# pic_tftp100_v2.net
KiCad netlist of a schematic drawn in EAGLE
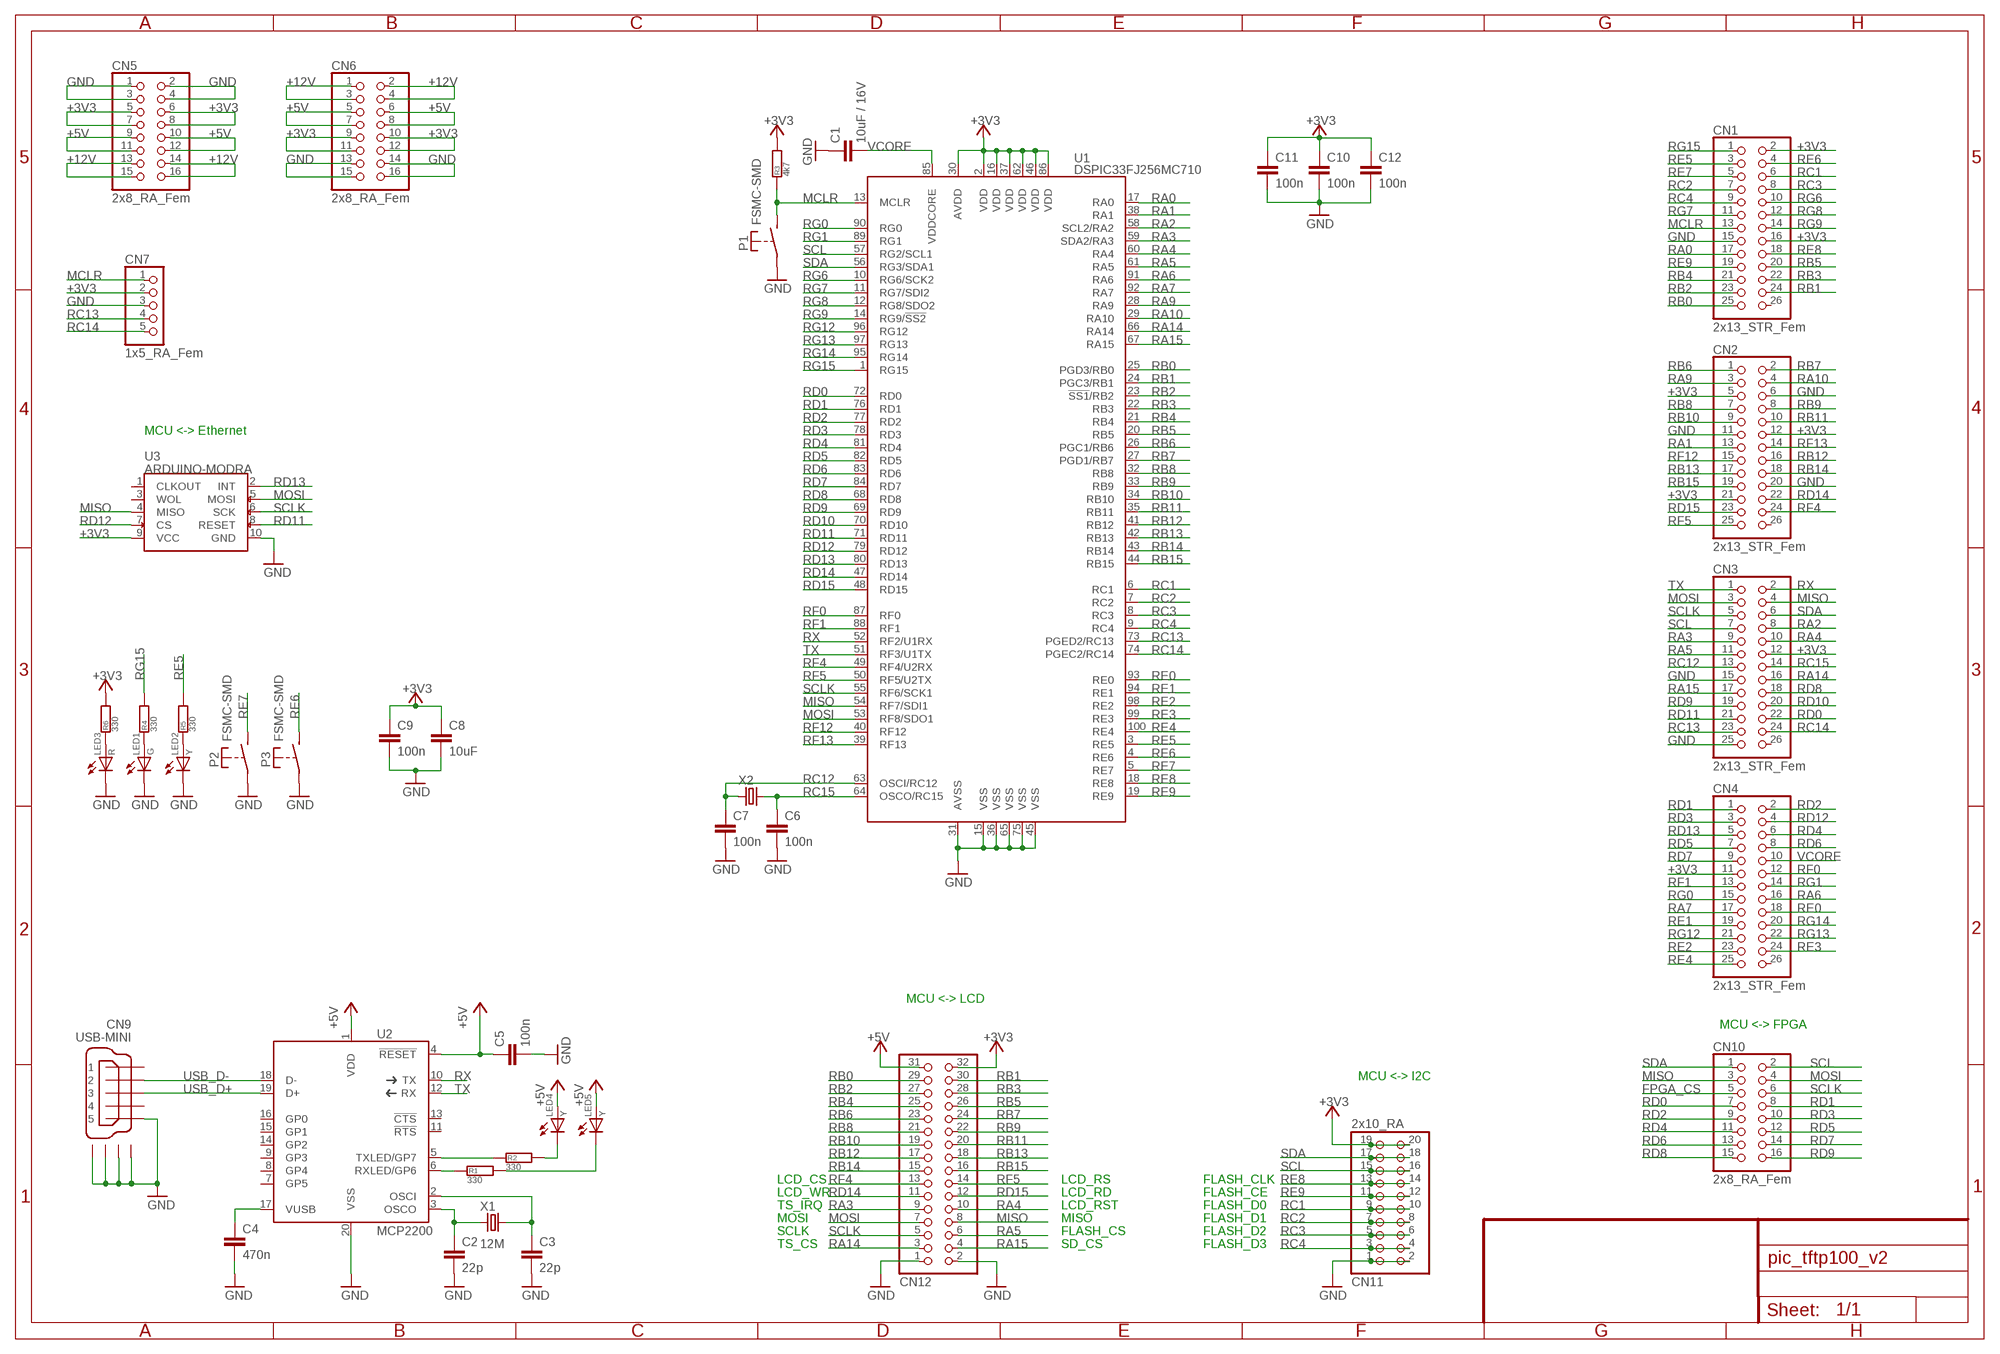
[diagram p0: schematic, sheet 1]

(export (version "E")
  (design (tool "Eeschema 10.0.6"))
  (components
    (comp (ref "C1")
      (value "10uF / 16V")
      (footprint "eagle-import:C1206")
      (libsource (lib "eagle-import") (part "CONDENSATEURSC1206"))
    )
    (comp (ref "C2")
      (value "22p")
      (footprint "eagle-import:C1206")
      (libsource (lib "eagle-import") (part "CONDENSATEURSC1206"))
    )
    (comp (ref "C3")
      (value "22p")
      (footprint "eagle-import:C1206")
      (libsource (lib "eagle-import") (part "CONDENSATEURSC1206"))
    )
    (comp (ref "C4")
      (value "470n")
      (footprint "eagle-import:C1206")
      (libsource (lib "eagle-import") (part "CONDENSATEURSC1206"))
    )
    (comp (ref "C5")
      (value "100n")
      (footprint "eagle-import:C1206")
      (libsource (lib "eagle-import") (part "CONDENSATEURSC1206"))
    )
    (comp (ref "C6")
      (value "100n")
      (footprint "eagle-import:C1206")
      (libsource (lib "eagle-import") (part "CONDENSATEURSC1206"))
    )
    (comp (ref "C7")
      (value "100n")
      (footprint "eagle-import:C1206")
      (libsource (lib "eagle-import") (part "CONDENSATEURSC1206"))
    )
    (comp (ref "C8")
      (value "10uF")
      (footprint "eagle-import:C1206")
      (libsource (lib "eagle-import") (part "CAPAC1206"))
    )
    (comp (ref "C9")
      (value "100n")
      (footprint "eagle-import:C1206")
      (libsource (lib "eagle-import") (part "CONDENSATEURSC1206"))
    )
    (comp (ref "C10")
      (value "100n")
      (footprint "eagle-import:C1206")
      (libsource (lib "eagle-import") (part "CONDENSATEURSC1206"))
    )
    (comp (ref "C11")
      (value "100n")
      (footprint "eagle-import:C1206")
      (libsource (lib "eagle-import") (part "CONDENSATEURSC1206"))
    )
    (comp (ref "C12")
      (value "100n")
      (footprint "eagle-import:C1206")
      (libsource (lib "eagle-import") (part "CONDENSATEURSC1206"))
    )
    (comp (ref "CN1")
      (value "2x13_STR_Fem")
      (footprint "eagle-import:2X13")
      (libsource (lib "eagle-import") (part "PINHD-2X13_2.54"))
    )
    (comp (ref "CN2")
      (value "2x13_STR_Fem")
      (footprint "eagle-import:2X13")
      (libsource (lib "eagle-import") (part "PINHD-2X13_2.54"))
    )
    (comp (ref "CN3")
      (value "2x13_STR_Fem")
      (footprint "eagle-import:2X13")
      (libsource (lib "eagle-import") (part "PINHD-2X13_2.54"))
    )
    (comp (ref "CN4")
      (value "2x13_STR_Fem")
      (footprint "eagle-import:2X13")
      (libsource (lib "eagle-import") (part "PINHD-2X13_2.54"))
    )
    (comp (ref "CN5")
      (value "2x8_RA_Fem")
      (footprint "eagle-import:2X08_90")
      (libsource (lib "eagle-import") (part "PINHD-2X8_2.54-90°"))
    )
    (comp (ref "CN6")
      (value "2x8_RA_Fem")
      (footprint "eagle-import:2X08_90")
      (libsource (lib "eagle-import") (part "PINHD-2X8_2.54-90°"))
    )
    (comp (ref "CN7")
      (value "1x5_RA_Fem")
      (footprint "eagle-import:1X05_90")
      (libsource (lib "eagle-import") (part "PINHD-1X5_2.54-90°"))
    )
    (comp (ref "CN9")
      (value "USB-MINI")
      (footprint "eagle-import:USB-MINI-SMT")
      (libsource (lib "eagle-import") (part "USB-MINI"))
    )
    (comp (ref "CN10")
      (value "2x8_RA_Fem")
      (footprint "eagle-import:2X08_90")
      (libsource (lib "eagle-import") (part "PINHD-2X8_2.54-90°"))
    )
    (comp (ref "CN11")
      (value "2x10_RA")
      (footprint "eagle-import:2X10_90")
      (libsource (lib "eagle-import") (part "PINHD-2X10_2.54-90°"))
    )
    (comp (ref "CN12")
      (value "PINHD-2X16_2.54-90°")
      (footprint "eagle-import:2X16_90")
      (libsource (lib "eagle-import") (part "PINHD-2X16_2.54-90°"))
    )
    (comp (ref "LED1")
      (value "G")
      (footprint "eagle-import:LED3MM")
      (libsource (lib "eagle-import") (part "LED3MM"))
    )
    (comp (ref "LED2")
      (value "Y")
      (footprint "eagle-import:LED3MM")
      (libsource (lib "eagle-import") (part "LED3MM"))
    )
    (comp (ref "LED3")
      (value "R")
      (footprint "eagle-import:LED3MM")
      (libsource (lib "eagle-import") (part "LED3MM"))
    )
    (comp (ref "LED4")
      (value "Y")
      (footprint "eagle-import:LED3MM")
      (libsource (lib "eagle-import") (part "LED3MM"))
    )
    (comp (ref "LED5")
      (value "Y")
      (footprint "eagle-import:LED3MM")
      (libsource (lib "eagle-import") (part "LED3MM"))
    )
    (comp (ref "P1")
      (value "FSMC-SMD")
      (footprint "eagle-import:FSMC-SMD")
      (libsource (lib "eagle-import") (part "FSMC-SMD"))
    )
    (comp (ref "P2")
      (value "FSMC-SMD")
      (footprint "eagle-import:FSMC-SMD")
      (libsource (lib "eagle-import") (part "FSMC-SMD"))
    )
    (comp (ref "P3")
      (value "FSMC-SMD")
      (footprint "eagle-import:FSMC-SMD")
      (libsource (lib "eagle-import") (part "FSMC-SMD"))
    )
    (comp (ref "R1")
      (value "330")
      (footprint "eagle-import:R1206")
      (libsource (lib "eagle-import") (part "RESISTANCESR1206"))
    )
    (comp (ref "R2")
      (value "330")
      (footprint "eagle-import:R1206")
      (libsource (lib "eagle-import") (part "RESISTANCESR1206"))
    )
    (comp (ref "R3")
      (value "4k7")
      (footprint "eagle-import:R1206")
      (libsource (lib "eagle-import") (part "RESISTANCESR1206"))
    )
    (comp (ref "R4")
      (value "330")
      (footprint "eagle-import:R1206")
      (libsource (lib "eagle-import") (part "RESISTANCESR1206"))
    )
    (comp (ref "R5")
      (value "330")
      (footprint "eagle-import:R1206")
      (libsource (lib "eagle-import") (part "RESISTANCESR1206"))
    )
    (comp (ref "R6")
      (value "330")
      (footprint "eagle-import:R1206")
      (libsource (lib "eagle-import") (part "RESISTANCESR1206"))
    )
    (comp (ref "U1")
      (value "DSPIC33FJ256MC710")
      (footprint "eagle-import:TQFP100")
      (libsource (lib "eagle-import") (part "DSPIC33FJ256MC710"))
    )
    (comp (ref "U2")
      (value "MCP2200")
      (footprint "eagle-import:SOIC20L")
      (libsource (lib "eagle-import") (part "MCP2200"))
    )
    (comp (ref "U3")
      (value "ARDUINO-MODRA")
      (footprint "eagle-import:ARDUINO_MOD_RIGHT_ANGLE")
      (libsource (lib "eagle-import") (part "ARDUINO-MODRA"))
    )
    (comp (ref "X1")
      (value "12M")
      (footprint "eagle-import:SMD2_50X32")
      (libsource (lib "eagle-import") (part "CRYSTALSMD2_50X32"))
    )
    (comp (ref "X2")
      (value "CRYSTALSMD2_50X32")
      (footprint "eagle-import:SMD2_50X32")
      (libsource (lib "eagle-import") (part "CRYSTALSMD2_50X32"))
    )
  )
  (nets
    (net (code "1") (name "+3V3") (class "Default")
      (node (ref "C10") (pin "1") (pinfunction "1_1") (pintype "passive"))
      (node (ref "C11") (pin "1") (pinfunction "1_1") (pintype "passive"))
      (node (ref "C12") (pin "1") (pinfunction "1_1") (pintype "passive"))
      (node (ref "C8") (pin "1") (pinfunction "1_1") (pintype "passive"))
      (node (ref "C9") (pin "1") (pinfunction "1_1") (pintype "passive"))
      (node (ref "CN1") (pin "16") (pinfunction "16_16") (pintype "passive"))
      (node (ref "CN1") (pin "2") (pinfunction "2_2") (pintype "passive"))
      (node (ref "CN11") (pin "19") (pinfunction "19_19") (pintype "passive"))
      (node (ref "CN11") (pin "20") (pinfunction "20_20") (pintype "passive"))
      (node (ref "CN12") (pin "32") (pinfunction "32_32") (pintype "passive"))
      (node (ref "CN2") (pin "12") (pinfunction "12_12") (pintype "passive"))
      (node (ref "CN2") (pin "21") (pinfunction "21_21") (pintype "passive"))
      (node (ref "CN2") (pin "5") (pinfunction "5_5") (pintype "passive"))
      (node (ref "CN3") (pin "12") (pinfunction "12_12") (pintype "passive"))
      (node (ref "CN4") (pin "11") (pinfunction "11_11") (pintype "passive"))
      (node (ref "CN5") (pin "5") (pinfunction "5_5") (pintype "passive"))
      (node (ref "CN5") (pin "6") (pinfunction "6_6") (pintype "passive"))
      (node (ref "CN5") (pin "7") (pinfunction "7_7") (pintype "passive"))
      (node (ref "CN5") (pin "8") (pinfunction "8_8") (pintype "passive"))
      (node (ref "CN6") (pin "10") (pinfunction "10_10") (pintype "passive"))
      (node (ref "CN6") (pin "11") (pinfunction "11_11") (pintype "passive"))
      (node (ref "CN6") (pin "12") (pinfunction "12_12") (pintype "passive"))
      (node (ref "CN6") (pin "9") (pinfunction "9_9") (pintype "passive"))
      (node (ref "CN7") (pin "2") (pinfunction "2_2") (pintype "passive"))
      (node (ref "R3") (pin "2") (pinfunction "2_2") (pintype "passive"))
      (node (ref "R6") (pin "2") (pinfunction "2_2") (pintype "passive"))
      (node (ref "U1") (pin "16") (pinfunction "VDD_16") (pintype "power_in"))
      (node (ref "U1") (pin "2") (pinfunction "VDD_2") (pintype "power_in"))
      (node (ref "U1") (pin "30") (pinfunction "AVDD_30") (pintype "power_in"))
      (node (ref "U1") (pin "37") (pinfunction "VDD_37") (pintype "power_in"))
      (node (ref "U1") (pin "46") (pinfunction "VDD_46") (pintype "power_in"))
      (node (ref "U1") (pin "62") (pinfunction "VDD_62") (pintype "power_in"))
      (node (ref "U1") (pin "86") (pinfunction "VDD_86") (pintype "power_in"))
      (node (ref "U3") (pin "9") (pinfunction "VCC_9") (pintype "power_in"))
    )
    (net (code "2") (name "+5V") (class "Default")
      (node (ref "C5") (pin "1") (pinfunction "1_1") (pintype "passive"))
      (node (ref "CN12") (pin "31") (pinfunction "31_31") (pintype "passive"))
      (node (ref "CN5") (pin "10") (pinfunction "10_10") (pintype "passive"))
      (node (ref "CN5") (pin "11") (pinfunction "11_11") (pintype "passive"))
      (node (ref "CN5") (pin "12") (pinfunction "12_12") (pintype "passive"))
      (node (ref "CN5") (pin "9") (pinfunction "9_9") (pintype "passive"))
      (node (ref "CN6") (pin "5") (pinfunction "5_5") (pintype "passive"))
      (node (ref "CN6") (pin "6") (pinfunction "6_6") (pintype "passive"))
      (node (ref "CN6") (pin "7") (pinfunction "7_7") (pintype "passive"))
      (node (ref "CN6") (pin "8") (pinfunction "8_8") (pintype "passive"))
      (node (ref "LED4") (pin "A") (pinfunction "A_A") (pintype "passive"))
      (node (ref "LED5") (pin "A") (pinfunction "A_A") (pintype "passive"))
      (node (ref "U2") (pin "1") (pinfunction "VDD_1") (pintype "power_in"))
      (node (ref "U2") (pin "4") (pinfunction "~{RESET}_4") (pintype "input"))
    )
    (net (code "3") (name "/+12V") (class "Default")
      (node (ref "CN5") (pin "13") (pinfunction "13_13") (pintype "passive"))
      (node (ref "CN5") (pin "14") (pinfunction "14_14") (pintype "passive"))
      (node (ref "CN5") (pin "15") (pinfunction "15_15") (pintype "passive"))
      (node (ref "CN5") (pin "16") (pinfunction "16_16") (pintype "passive"))
      (node (ref "CN6") (pin "1") (pinfunction "1_1") (pintype "passive"))
      (node (ref "CN6") (pin "2") (pinfunction "2_2") (pintype "passive"))
      (node (ref "CN6") (pin "3") (pinfunction "3_3") (pintype "passive"))
      (node (ref "CN6") (pin "4") (pinfunction "4_4") (pintype "passive"))
    )
    (net (code "4") (name "/FPGA_CS") (class "Default")
      (node (ref "CN10") (pin "5") (pinfunction "5_5") (pintype "passive"))
    )
    (net (code "5") (name "/MCLR") (class "Default")
      (node (ref "CN1") (pin "13") (pinfunction "13_13") (pintype "passive"))
      (node (ref "CN7") (pin "1") (pinfunction "1_1") (pintype "passive"))
      (node (ref "P1") (pin "P$2") (pinfunction "S_P$2") (pintype "passive"))
      (node (ref "R3") (pin "1") (pinfunction "1_1") (pintype "passive"))
      (node (ref "U1") (pin "13") (pinfunction "MCLR_13") (pintype "bidirectional"))
    )
    (net (code "6") (name "/MISO") (class "Default")
      (node (ref "CN10") (pin "3") (pinfunction "3_3") (pintype "passive"))
      (node (ref "CN12") (pin "8") (pinfunction "8_8") (pintype "passive"))
      (node (ref "CN3") (pin "4") (pinfunction "4_4") (pintype "passive"))
      (node (ref "U1") (pin "54") (pinfunction "RF7/SDI1_54") (pintype "bidirectional"))
      (node (ref "U3") (pin "4") (pinfunction "MISO_4") (pintype "output"))
    )
    (net (code "7") (name "/MOSI") (class "Default")
      (node (ref "CN10") (pin "4") (pinfunction "4_4") (pintype "passive"))
      (node (ref "CN12") (pin "7") (pinfunction "7_7") (pintype "passive"))
      (node (ref "CN3") (pin "3") (pinfunction "3_3") (pintype "passive"))
      (node (ref "U1") (pin "53") (pinfunction "RF8/SDO1_53") (pintype "bidirectional"))
      (node (ref "U3") (pin "5") (pinfunction "MOSI_5") (pintype "input"))
    )
    (net (code "8") (name "/RA0") (class "Default")
      (node (ref "CN1") (pin "17") (pinfunction "17_17") (pintype "passive"))
      (node (ref "U1") (pin "17") (pinfunction "RA0_17") (pintype "bidirectional"))
    )
    (net (code "9") (name "/RA1") (class "Default")
      (node (ref "CN2") (pin "13") (pinfunction "13_13") (pintype "passive"))
      (node (ref "U1") (pin "38") (pinfunction "RA1_38") (pintype "bidirectional"))
    )
    (net (code "10") (name "/RA2") (class "Default")
      (node (ref "CN3") (pin "8") (pinfunction "8_8") (pintype "passive"))
      (node (ref "U1") (pin "58") (pinfunction "SCL2/RA2_58") (pintype "bidirectional"))
    )
    (net (code "11") (name "/RA3") (class "Default")
      (node (ref "CN12") (pin "9") (pinfunction "9_9") (pintype "passive"))
      (node (ref "CN3") (pin "9") (pinfunction "9_9") (pintype "passive"))
      (node (ref "U1") (pin "59") (pinfunction "SDA2/RA3_59") (pintype "bidirectional"))
    )
    (net (code "12") (name "/RA4") (class "Default")
      (node (ref "CN12") (pin "10") (pinfunction "10_10") (pintype "passive"))
      (node (ref "CN3") (pin "10") (pinfunction "10_10") (pintype "passive"))
      (node (ref "U1") (pin "60") (pinfunction "RA4_60") (pintype "bidirectional"))
    )
    (net (code "13") (name "/RA5") (class "Default")
      (node (ref "CN12") (pin "6") (pinfunction "6_6") (pintype "passive"))
      (node (ref "CN3") (pin "11") (pinfunction "11_11") (pintype "passive"))
      (node (ref "U1") (pin "61") (pinfunction "RA5_61") (pintype "bidirectional"))
    )
    (net (code "14") (name "/RA6") (class "Default")
      (node (ref "CN4") (pin "16") (pinfunction "16_16") (pintype "passive"))
      (node (ref "U1") (pin "91") (pinfunction "RA6_91") (pintype "bidirectional"))
    )
    (net (code "15") (name "/RA7") (class "Default")
      (node (ref "CN4") (pin "17") (pinfunction "17_17") (pintype "passive"))
      (node (ref "U1") (pin "92") (pinfunction "RA7_92") (pintype "bidirectional"))
    )
    (net (code "16") (name "/RA9") (class "Default")
      (node (ref "CN2") (pin "3") (pinfunction "3_3") (pintype "passive"))
      (node (ref "U1") (pin "28") (pinfunction "RA9_28") (pintype "bidirectional"))
    )
    (net (code "17") (name "/RA10") (class "Default")
      (node (ref "CN2") (pin "4") (pinfunction "4_4") (pintype "passive"))
      (node (ref "U1") (pin "29") (pinfunction "RA10_29") (pintype "bidirectional"))
    )
    (net (code "18") (name "/RA14") (class "Default")
      (node (ref "CN12") (pin "3") (pinfunction "3_3") (pintype "passive"))
      (node (ref "CN3") (pin "16") (pinfunction "16_16") (pintype "passive"))
      (node (ref "U1") (pin "66") (pinfunction "RA14_66") (pintype "bidirectional"))
    )
    (net (code "19") (name "/RA15") (class "Default")
      (node (ref "CN12") (pin "4") (pinfunction "4_4") (pintype "passive"))
      (node (ref "CN3") (pin "17") (pinfunction "17_17") (pintype "passive"))
      (node (ref "U1") (pin "67") (pinfunction "RA15_67") (pintype "bidirectional"))
    )
    (net (code "20") (name "/RB0") (class "Default")
      (node (ref "CN1") (pin "25") (pinfunction "25_25") (pintype "passive"))
      (node (ref "CN12") (pin "29") (pinfunction "29_29") (pintype "passive"))
      (node (ref "U1") (pin "25") (pinfunction "PGD3/RB0_25") (pintype "bidirectional"))
    )
    (net (code "21") (name "/RB1") (class "Default")
      (node (ref "CN1") (pin "24") (pinfunction "24_24") (pintype "passive"))
      (node (ref "CN12") (pin "30") (pinfunction "30_30") (pintype "passive"))
      (node (ref "U1") (pin "24") (pinfunction "PGC3/RB1_24") (pintype "bidirectional"))
    )
    (net (code "22") (name "/RB2") (class "Default")
      (node (ref "CN1") (pin "23") (pinfunction "23_23") (pintype "passive"))
      (node (ref "CN12") (pin "27") (pinfunction "27_27") (pintype "passive"))
      (node (ref "U1") (pin "23") (pinfunction "~{SS1}/RB2_23") (pintype "bidirectional"))
    )
    (net (code "23") (name "/RB3") (class "Default")
      (node (ref "CN1") (pin "22") (pinfunction "22_22") (pintype "passive"))
      (node (ref "CN12") (pin "28") (pinfunction "28_28") (pintype "passive"))
      (node (ref "U1") (pin "22") (pinfunction "RB3_22") (pintype "bidirectional"))
    )
    (net (code "24") (name "/RB4") (class "Default")
      (node (ref "CN1") (pin "21") (pinfunction "21_21") (pintype "passive"))
      (node (ref "CN12") (pin "25") (pinfunction "25_25") (pintype "passive"))
      (node (ref "U1") (pin "21") (pinfunction "RB4_21") (pintype "bidirectional"))
    )
    (net (code "25") (name "/RB5") (class "Default")
      (node (ref "CN1") (pin "20") (pinfunction "20_20") (pintype "passive"))
      (node (ref "CN12") (pin "26") (pinfunction "26_26") (pintype "passive"))
      (node (ref "U1") (pin "20") (pinfunction "RB5_20") (pintype "bidirectional"))
    )
    (net (code "26") (name "/RB6") (class "Default")
      (node (ref "CN12") (pin "23") (pinfunction "23_23") (pintype "passive"))
      (node (ref "CN2") (pin "1") (pinfunction "1_1") (pintype "passive"))
      (node (ref "U1") (pin "26") (pinfunction "PGC1/RB6_26") (pintype "bidirectional"))
    )
    (net (code "27") (name "/RB7") (class "Default")
      (node (ref "CN12") (pin "24") (pinfunction "24_24") (pintype "passive"))
      (node (ref "CN2") (pin "2") (pinfunction "2_2") (pintype "passive"))
      (node (ref "U1") (pin "27") (pinfunction "PGD1/RB7_27") (pintype "bidirectional"))
    )
    (net (code "28") (name "/RB8") (class "Default")
      (node (ref "CN12") (pin "21") (pinfunction "21_21") (pintype "passive"))
      (node (ref "CN2") (pin "7") (pinfunction "7_7") (pintype "passive"))
      (node (ref "U1") (pin "32") (pinfunction "RB8_32") (pintype "bidirectional"))
    )
    (net (code "29") (name "/RB9") (class "Default")
      (node (ref "CN12") (pin "22") (pinfunction "22_22") (pintype "passive"))
      (node (ref "CN2") (pin "8") (pinfunction "8_8") (pintype "passive"))
      (node (ref "U1") (pin "33") (pinfunction "RB9_33") (pintype "bidirectional"))
    )
    (net (code "30") (name "/RB10") (class "Default")
      (node (ref "CN12") (pin "19") (pinfunction "19_19") (pintype "passive"))
      (node (ref "CN2") (pin "9") (pinfunction "9_9") (pintype "passive"))
      (node (ref "U1") (pin "34") (pinfunction "RB10_34") (pintype "bidirectional"))
    )
    (net (code "31") (name "/RB11") (class "Default")
      (node (ref "CN12") (pin "20") (pinfunction "20_20") (pintype "passive"))
      (node (ref "CN2") (pin "10") (pinfunction "10_10") (pintype "passive"))
      (node (ref "U1") (pin "35") (pinfunction "RB11_35") (pintype "bidirectional"))
    )
    (net (code "32") (name "/RB12") (class "Default")
      (node (ref "CN12") (pin "17") (pinfunction "17_17") (pintype "passive"))
      (node (ref "CN2") (pin "16") (pinfunction "16_16") (pintype "passive"))
      (node (ref "U1") (pin "41") (pinfunction "RB12_41") (pintype "bidirectional"))
    )
    (net (code "33") (name "/RB13") (class "Default")
      (node (ref "CN12") (pin "18") (pinfunction "18_18") (pintype "passive"))
      (node (ref "CN2") (pin "17") (pinfunction "17_17") (pintype "passive"))
      (node (ref "U1") (pin "42") (pinfunction "RB13_42") (pintype "bidirectional"))
    )
    (net (code "34") (name "/RB14") (class "Default")
      (node (ref "CN12") (pin "15") (pinfunction "15_15") (pintype "passive"))
      (node (ref "CN2") (pin "18") (pinfunction "18_18") (pintype "passive"))
      (node (ref "U1") (pin "43") (pinfunction "RB14_43") (pintype "bidirectional"))
    )
    (net (code "35") (name "/RB15") (class "Default")
      (node (ref "CN12") (pin "16") (pinfunction "16_16") (pintype "passive"))
      (node (ref "CN2") (pin "19") (pinfunction "19_19") (pintype "passive"))
      (node (ref "U1") (pin "44") (pinfunction "RB15_44") (pintype "bidirectional"))
    )
    (net (code "36") (name "/RC1") (class "Default")
      (node (ref "CN1") (pin "6") (pinfunction "6_6") (pintype "passive"))
      (node (ref "CN11") (pin "10") (pinfunction "10_10") (pintype "passive"))
      (node (ref "CN11") (pin "9") (pinfunction "9_9") (pintype "passive"))
      (node (ref "U1") (pin "6") (pinfunction "RC1_6") (pintype "bidirectional"))
    )
    (net (code "37") (name "/RC2") (class "Default")
      (node (ref "CN1") (pin "7") (pinfunction "7_7") (pintype "passive"))
      (node (ref "CN11") (pin "7") (pinfunction "7_7") (pintype "passive"))
      (node (ref "CN11") (pin "8") (pinfunction "8_8") (pintype "passive"))
      (node (ref "U1") (pin "7") (pinfunction "RC2_7") (pintype "bidirectional"))
    )
    (net (code "38") (name "/RC3") (class "Default")
      (node (ref "CN1") (pin "8") (pinfunction "8_8") (pintype "passive"))
      (node (ref "CN11") (pin "5") (pinfunction "5_5") (pintype "passive"))
      (node (ref "CN11") (pin "6") (pinfunction "6_6") (pintype "passive"))
      (node (ref "U1") (pin "8") (pinfunction "RC3_8") (pintype "bidirectional"))
    )
    (net (code "39") (name "/RC4") (class "Default")
      (node (ref "CN1") (pin "9") (pinfunction "9_9") (pintype "passive"))
      (node (ref "CN11") (pin "3") (pinfunction "3_3") (pintype "passive"))
      (node (ref "CN11") (pin "4") (pinfunction "4_4") (pintype "passive"))
      (node (ref "U1") (pin "9") (pinfunction "RC4_9") (pintype "bidirectional"))
    )
    (net (code "40") (name "/RC12") (class "Default")
      (node (ref "C7") (pin "1") (pinfunction "1_1") (pintype "passive"))
      (node (ref "CN3") (pin "13") (pinfunction "13_13") (pintype "passive"))
      (node (ref "U1") (pin "63") (pinfunction "OSCI/RC12_63") (pintype "input"))
      (node (ref "X2") (pin "1") (pinfunction "1_1") (pintype "passive"))
    )
    (net (code "41") (name "/RC13") (class "Default")
      (node (ref "CN3") (pin "23") (pinfunction "23_23") (pintype "passive"))
      (node (ref "CN7") (pin "4") (pinfunction "4_4") (pintype "passive"))
      (node (ref "U1") (pin "73") (pinfunction "PGED2/RC13_73") (pintype "bidirectional"))
    )
    (net (code "42") (name "/RC14") (class "Default")
      (node (ref "CN3") (pin "24") (pinfunction "24_24") (pintype "passive"))
      (node (ref "CN7") (pin "5") (pinfunction "5_5") (pintype "passive"))
      (node (ref "U1") (pin "74") (pinfunction "PGEC2/RC14_74") (pintype "bidirectional"))
    )
    (net (code "43") (name "/RC15") (class "Default")
      (node (ref "C6") (pin "1") (pinfunction "1_1") (pintype "passive"))
      (node (ref "CN3") (pin "14") (pinfunction "14_14") (pintype "passive"))
      (node (ref "U1") (pin "64") (pinfunction "OSCO/RC15_64") (pintype "output"))
      (node (ref "X2") (pin "2") (pinfunction "2_2") (pintype "passive"))
    )
    (net (code "44") (name "/RD0") (class "Default")
      (node (ref "CN10") (pin "7") (pinfunction "7_7") (pintype "passive"))
      (node (ref "CN3") (pin "22") (pinfunction "22_22") (pintype "passive"))
      (node (ref "U1") (pin "72") (pinfunction "RD0_72") (pintype "bidirectional"))
    )
    (net (code "45") (name "/RD1") (class "Default")
      (node (ref "CN10") (pin "8") (pinfunction "8_8") (pintype "passive"))
      (node (ref "CN4") (pin "1") (pinfunction "1_1") (pintype "passive"))
      (node (ref "U1") (pin "76") (pinfunction "RD1_76") (pintype "bidirectional"))
    )
    (net (code "46") (name "/RD2") (class "Default")
      (node (ref "CN10") (pin "9") (pinfunction "9_9") (pintype "passive"))
      (node (ref "CN4") (pin "2") (pinfunction "2_2") (pintype "passive"))
      (node (ref "U1") (pin "77") (pinfunction "RD2_77") (pintype "bidirectional"))
    )
    (net (code "47") (name "/RD3") (class "Default")
      (node (ref "CN10") (pin "10") (pinfunction "10_10") (pintype "passive"))
      (node (ref "CN4") (pin "3") (pinfunction "3_3") (pintype "passive"))
      (node (ref "U1") (pin "78") (pinfunction "RD3_78") (pintype "bidirectional"))
    )
    (net (code "48") (name "/RD4") (class "Default")
      (node (ref "CN10") (pin "11") (pinfunction "11_11") (pintype "passive"))
      (node (ref "CN4") (pin "6") (pinfunction "6_6") (pintype "passive"))
      (node (ref "U1") (pin "81") (pinfunction "RD4_81") (pintype "bidirectional"))
    )
    (net (code "49") (name "/RD5") (class "Default")
      (node (ref "CN10") (pin "12") (pinfunction "12_12") (pintype "passive"))
      (node (ref "CN4") (pin "7") (pinfunction "7_7") (pintype "passive"))
      (node (ref "U1") (pin "82") (pinfunction "RD5_82") (pintype "bidirectional"))
    )
    (net (code "50") (name "/RD6") (class "Default")
      (node (ref "CN10") (pin "13") (pinfunction "13_13") (pintype "passive"))
      (node (ref "CN4") (pin "8") (pinfunction "8_8") (pintype "passive"))
      (node (ref "U1") (pin "83") (pinfunction "RD6_83") (pintype "bidirectional"))
    )
    (net (code "51") (name "/RD7") (class "Default")
      (node (ref "CN10") (pin "14") (pinfunction "14_14") (pintype "passive"))
      (node (ref "CN4") (pin "9") (pinfunction "9_9") (pintype "passive"))
      (node (ref "U1") (pin "84") (pinfunction "RD7_84") (pintype "bidirectional"))
    )
    (net (code "52") (name "/RD8") (class "Default")
      (node (ref "CN10") (pin "15") (pinfunction "15_15") (pintype "passive"))
      (node (ref "CN3") (pin "18") (pinfunction "18_18") (pintype "passive"))
      (node (ref "U1") (pin "68") (pinfunction "RD8_68") (pintype "bidirectional"))
    )
    (net (code "53") (name "/RD9") (class "Default")
      (node (ref "CN10") (pin "16") (pinfunction "16_16") (pintype "passive"))
      (node (ref "CN3") (pin "19") (pinfunction "19_19") (pintype "passive"))
      (node (ref "U1") (pin "69") (pinfunction "RD9_69") (pintype "bidirectional"))
    )
    (net (code "54") (name "/RD10") (class "Default")
      (node (ref "CN3") (pin "20") (pinfunction "20_20") (pintype "passive"))
      (node (ref "U1") (pin "70") (pinfunction "RD10_70") (pintype "bidirectional"))
    )
    (net (code "55") (name "/RD11") (class "Default")
      (node (ref "CN3") (pin "21") (pinfunction "21_21") (pintype "passive"))
      (node (ref "U1") (pin "71") (pinfunction "RD11_71") (pintype "bidirectional"))
      (node (ref "U3") (pin "8") (pinfunction "RESET_8") (pintype "input"))
    )
    (net (code "56") (name "/RD12") (class "Default")
      (node (ref "CN4") (pin "4") (pinfunction "4_4") (pintype "passive"))
      (node (ref "U1") (pin "79") (pinfunction "RD12_79") (pintype "bidirectional"))
      (node (ref "U3") (pin "7") (pinfunction "CS_7") (pintype "input"))
    )
    (net (code "57") (name "/RD13") (class "Default")
      (node (ref "CN4") (pin "5") (pinfunction "5_5") (pintype "passive"))
      (node (ref "U1") (pin "80") (pinfunction "RD13_80") (pintype "bidirectional"))
      (node (ref "U3") (pin "2") (pinfunction "INT_2") (pintype "output"))
    )
    (net (code "58") (name "/RD14") (class "Default")
      (node (ref "CN12") (pin "11") (pinfunction "11_11") (pintype "passive"))
      (node (ref "CN2") (pin "22") (pinfunction "22_22") (pintype "passive"))
      (node (ref "U1") (pin "47") (pinfunction "RD14_47") (pintype "bidirectional"))
    )
    (net (code "59") (name "/RD15") (class "Default")
      (node (ref "CN12") (pin "12") (pinfunction "12_12") (pintype "passive"))
      (node (ref "CN2") (pin "23") (pinfunction "23_23") (pintype "passive"))
      (node (ref "U1") (pin "48") (pinfunction "RD15_48") (pintype "bidirectional"))
    )
    (net (code "60") (name "/RE0") (class "Default")
      (node (ref "CN4") (pin "18") (pinfunction "18_18") (pintype "passive"))
      (node (ref "U1") (pin "93") (pinfunction "RE0_93") (pintype "bidirectional"))
    )
    (net (code "61") (name "/RE1") (class "Default")
      (node (ref "CN4") (pin "19") (pinfunction "19_19") (pintype "passive"))
      (node (ref "U1") (pin "94") (pinfunction "RE1_94") (pintype "bidirectional"))
    )
    (net (code "62") (name "/RE2") (class "Default")
      (node (ref "CN4") (pin "23") (pinfunction "23_23") (pintype "passive"))
      (node (ref "U1") (pin "98") (pinfunction "RE2_98") (pintype "bidirectional"))
    )
    (net (code "63") (name "/RE3") (class "Default")
      (node (ref "CN4") (pin "24") (pinfunction "24_24") (pintype "passive"))
      (node (ref "U1") (pin "99") (pinfunction "RE3_99") (pintype "bidirectional"))
    )
    (net (code "64") (name "/RE4") (class "Default")
      (node (ref "CN4") (pin "25") (pinfunction "25_25") (pintype "passive"))
      (node (ref "U1") (pin "100") (pinfunction "RE4_100") (pintype "bidirectional"))
    )
    (net (code "65") (name "/RE5") (class "Default")
      (node (ref "CN1") (pin "3") (pinfunction "3_3") (pintype "passive"))
      (node (ref "R5") (pin "2") (pinfunction "2_2") (pintype "passive"))
      (node (ref "U1") (pin "3") (pinfunction "RE5_3") (pintype "bidirectional"))
    )
    (net (code "66") (name "/RE6") (class "Default")
      (node (ref "CN1") (pin "4") (pinfunction "4_4") (pintype "passive"))
      (node (ref "P3") (pin "P$2") (pinfunction "S_P$2") (pintype "passive"))
      (node (ref "U1") (pin "4") (pinfunction "RE6_4") (pintype "bidirectional"))
    )
    (net (code "67") (name "/RE7") (class "Default")
      (node (ref "CN1") (pin "5") (pinfunction "5_5") (pintype "passive"))
      (node (ref "P2") (pin "P$2") (pinfunction "S_P$2") (pintype "passive"))
      (node (ref "U1") (pin "5") (pinfunction "RE7_5") (pintype "bidirectional"))
    )
    (net (code "68") (name "/RE8") (class "Default")
      (node (ref "CN1") (pin "18") (pinfunction "18_18") (pintype "passive"))
      (node (ref "CN11") (pin "13") (pinfunction "13_13") (pintype "passive"))
      (node (ref "CN11") (pin "14") (pinfunction "14_14") (pintype "passive"))
      (node (ref "U1") (pin "18") (pinfunction "RE8_18") (pintype "bidirectional"))
    )
    (net (code "69") (name "/RE9") (class "Default")
      (node (ref "CN1") (pin "19") (pinfunction "19_19") (pintype "passive"))
      (node (ref "CN11") (pin "11") (pinfunction "11_11") (pintype "passive"))
      (node (ref "CN11") (pin "12") (pinfunction "12_12") (pintype "passive"))
      (node (ref "U1") (pin "19") (pinfunction "RE9_19") (pintype "bidirectional"))
    )
    (net (code "70") (name "/RF0") (class "Default")
      (node (ref "CN4") (pin "12") (pinfunction "12_12") (pintype "passive"))
      (node (ref "U1") (pin "87") (pinfunction "RF0_87") (pintype "bidirectional"))
    )
    (net (code "71") (name "/RF1") (class "Default")
      (node (ref "CN4") (pin "13") (pinfunction "13_13") (pintype "passive"))
      (node (ref "U1") (pin "88") (pinfunction "RF1_88") (pintype "bidirectional"))
    )
    (net (code "72") (name "/RF4") (class "Default")
      (node (ref "CN12") (pin "13") (pinfunction "13_13") (pintype "passive"))
      (node (ref "CN2") (pin "24") (pinfunction "24_24") (pintype "passive"))
      (node (ref "U1") (pin "49") (pinfunction "RF4/U2RX_49") (pintype "bidirectional"))
    )
    (net (code "73") (name "/RF5") (class "Default")
      (node (ref "CN12") (pin "14") (pinfunction "14_14") (pintype "passive"))
      (node (ref "CN2") (pin "25") (pinfunction "25_25") (pintype "passive"))
      (node (ref "U1") (pin "50") (pinfunction "RF5/U2TX_50") (pintype "bidirectional"))
    )
    (net (code "74") (name "/RF12") (class "Default")
      (node (ref "CN2") (pin "15") (pinfunction "15_15") (pintype "passive"))
      (node (ref "U1") (pin "40") (pinfunction "RF12_40") (pintype "bidirectional"))
    )
    (net (code "75") (name "/RF13") (class "Default")
      (node (ref "CN2") (pin "14") (pinfunction "14_14") (pintype "passive"))
      (node (ref "U1") (pin "39") (pinfunction "RF13_39") (pintype "bidirectional"))
    )
    (net (code "76") (name "/RG0") (class "Default")
      (node (ref "CN4") (pin "15") (pinfunction "15_15") (pintype "passive"))
      (node (ref "U1") (pin "90") (pinfunction "RG0_90") (pintype "bidirectional"))
    )
    (net (code "77") (name "/RG1") (class "Default")
      (node (ref "CN4") (pin "14") (pinfunction "14_14") (pintype "passive"))
      (node (ref "U1") (pin "89") (pinfunction "RG1_89") (pintype "bidirectional"))
    )
    (net (code "78") (name "/RG6") (class "Default")
      (node (ref "CN1") (pin "10") (pinfunction "10_10") (pintype "passive"))
      (node (ref "U1") (pin "10") (pinfunction "RG6/SCK2_10") (pintype "bidirectional"))
    )
    (net (code "79") (name "/RG7") (class "Default")
      (node (ref "CN1") (pin "11") (pinfunction "11_11") (pintype "passive"))
      (node (ref "U1") (pin "11") (pinfunction "RG7/SDI2_11") (pintype "bidirectional"))
    )
    (net (code "80") (name "/RG8") (class "Default")
      (node (ref "CN1") (pin "12") (pinfunction "12_12") (pintype "passive"))
      (node (ref "U1") (pin "12") (pinfunction "RG8/SDO2_12") (pintype "bidirectional"))
    )
    (net (code "81") (name "/RG9") (class "Default")
      (node (ref "CN1") (pin "14") (pinfunction "14_14") (pintype "passive"))
      (node (ref "U1") (pin "14") (pinfunction "RG9/~{SS2}_14") (pintype "bidirectional"))
    )
    (net (code "82") (name "/RG12") (class "Default")
      (node (ref "CN4") (pin "21") (pinfunction "21_21") (pintype "passive"))
      (node (ref "U1") (pin "96") (pinfunction "RG12_96") (pintype "bidirectional"))
    )
    (net (code "83") (name "/RG13") (class "Default")
      (node (ref "CN4") (pin "22") (pinfunction "22_22") (pintype "passive"))
      (node (ref "U1") (pin "97") (pinfunction "RG13_97") (pintype "bidirectional"))
    )
    (net (code "84") (name "/RG14") (class "Default")
      (node (ref "CN4") (pin "20") (pinfunction "20_20") (pintype "passive"))
      (node (ref "U1") (pin "95") (pinfunction "RG14_95") (pintype "bidirectional"))
    )
    (net (code "85") (name "/RG15") (class "Default")
      (node (ref "CN1") (pin "1") (pinfunction "1_1") (pintype "passive"))
      (node (ref "R4") (pin "2") (pinfunction "2_2") (pintype "passive"))
      (node (ref "U1") (pin "1") (pinfunction "RG15_1") (pintype "bidirectional"))
    )
    (net (code "86") (name "/RX") (class "Default")
      (node (ref "CN3") (pin "2") (pinfunction "2_2") (pintype "passive"))
      (node (ref "U1") (pin "52") (pinfunction "RF2/U1RX_52") (pintype "bidirectional"))
      (node (ref "U2") (pin "10") (pinfunction "TX_10") (pintype "bidirectional"))
    )
    (net (code "87") (name "/SCL") (class "Default")
      (node (ref "CN10") (pin "2") (pinfunction "2_2") (pintype "passive"))
      (node (ref "CN11") (pin "15") (pinfunction "15_15") (pintype "passive"))
      (node (ref "CN11") (pin "16") (pinfunction "16_16") (pintype "passive"))
      (node (ref "CN3") (pin "7") (pinfunction "7_7") (pintype "passive"))
      (node (ref "U1") (pin "57") (pinfunction "RG2/SCL1_57") (pintype "bidirectional"))
    )
    (net (code "88") (name "/SCLK") (class "Default")
      (node (ref "CN10") (pin "6") (pinfunction "6_6") (pintype "passive"))
      (node (ref "CN12") (pin "5") (pinfunction "5_5") (pintype "passive"))
      (node (ref "CN3") (pin "5") (pinfunction "5_5") (pintype "passive"))
      (node (ref "U1") (pin "55") (pinfunction "RF6/SCK1_55") (pintype "bidirectional"))
      (node (ref "U3") (pin "6") (pinfunction "SCK_6") (pintype "input"))
    )
    (net (code "89") (name "/SDA") (class "Default")
      (node (ref "CN10") (pin "1") (pinfunction "1_1") (pintype "passive"))
      (node (ref "CN11") (pin "17") (pinfunction "17_17") (pintype "passive"))
      (node (ref "CN11") (pin "18") (pinfunction "18_18") (pintype "passive"))
      (node (ref "CN3") (pin "6") (pinfunction "6_6") (pintype "passive"))
      (node (ref "U1") (pin "56") (pinfunction "RG3/SDA1_56") (pintype "bidirectional"))
    )
    (net (code "90") (name "/TX") (class "Default")
      (node (ref "CN3") (pin "1") (pinfunction "1_1") (pintype "passive"))
      (node (ref "U1") (pin "51") (pinfunction "RF3/U1TX_51") (pintype "bidirectional"))
      (node (ref "U2") (pin "12") (pinfunction "RX_12") (pintype "input"))
    )
    (net (code "91") (name "/USB_D+") (class "Default")
      (node (ref "CN9") (pin "3") (pinfunction "3_3") (pintype "input"))
      (node (ref "U2") (pin "19") (pinfunction "D+_19") (pintype "bidirectional"))
    )
    (net (code "92") (name "/USB_D-") (class "Default")
      (node (ref "CN9") (pin "2") (pinfunction "2_2") (pintype "input"))
      (node (ref "U2") (pin "18") (pinfunction "D-_18") (pintype "bidirectional"))
    )
    (net (code "93") (name "/VCORE") (class "Default")
      (node (ref "C1") (pin "2") (pinfunction "2_2") (pintype "passive"))
      (node (ref "CN4") (pin "10") (pinfunction "10_10") (pintype "passive"))
      (node (ref "U1") (pin "85") (pinfunction "VDDCORE_85") (pintype "power_in"))
    )
    (net (code "94") (name "GND") (class "Default")
      (node (ref "C1") (pin "1") (pinfunction "1_1") (pintype "passive"))
      (node (ref "C10") (pin "2") (pinfunction "2_2") (pintype "passive"))
      (node (ref "C11") (pin "2") (pinfunction "2_2") (pintype "passive"))
      (node (ref "C12") (pin "2") (pinfunction "2_2") (pintype "passive"))
      (node (ref "C2") (pin "2") (pinfunction "2_2") (pintype "passive"))
      (node (ref "C3") (pin "2") (pinfunction "2_2") (pintype "passive"))
      (node (ref "C4") (pin "2") (pinfunction "2_2") (pintype "passive"))
      (node (ref "C5") (pin "2") (pinfunction "2_2") (pintype "passive"))
      (node (ref "C6") (pin "2") (pinfunction "2_2") (pintype "passive"))
      (node (ref "C7") (pin "2") (pinfunction "2_2") (pintype "passive"))
      (node (ref "C8") (pin "2") (pinfunction "2_2") (pintype "passive"))
      (node (ref "C9") (pin "2") (pinfunction "2_2") (pintype "passive"))
      (node (ref "CN1") (pin "15") (pinfunction "15_15") (pintype "passive"))
      (node (ref "CN11") (pin "1") (pinfunction "1_1") (pintype "passive"))
      (node (ref "CN11") (pin "2") (pinfunction "2_2") (pintype "passive"))
      (node (ref "CN12") (pin "1") (pinfunction "1_1") (pintype "passive"))
      (node (ref "CN12") (pin "2") (pinfunction "2_2") (pintype "passive"))
      (node (ref "CN2") (pin "11") (pinfunction "11_11") (pintype "passive"))
      (node (ref "CN2") (pin "20") (pinfunction "20_20") (pintype "passive"))
      (node (ref "CN2") (pin "6") (pinfunction "6_6") (pintype "passive"))
      (node (ref "CN3") (pin "15") (pinfunction "15_15") (pintype "passive"))
      (node (ref "CN3") (pin "25") (pinfunction "25_25") (pintype "passive"))
      (node (ref "CN5") (pin "1") (pinfunction "1_1") (pintype "passive"))
      (node (ref "CN5") (pin "2") (pinfunction "2_2") (pintype "passive"))
      (node (ref "CN5") (pin "3") (pinfunction "3_3") (pintype "passive"))
      (node (ref "CN5") (pin "4") (pinfunction "4_4") (pintype "passive"))
      (node (ref "CN6") (pin "13") (pinfunction "13_13") (pintype "passive"))
      (node (ref "CN6") (pin "14") (pinfunction "14_14") (pintype "passive"))
      (node (ref "CN6") (pin "15") (pinfunction "15_15") (pintype "passive"))
      (node (ref "CN6") (pin "16") (pinfunction "16_16") (pintype "passive"))
      (node (ref "CN7") (pin "3") (pinfunction "3_3") (pintype "passive"))
      (node (ref "CN9") (pin "5") (pinfunction "5_5") (pintype "input"))
      (node (ref "CN9") (pin "M1") (pinfunction "P$1_M1") (pintype "bidirectional"))
      (node (ref "CN9") (pin "M2") (pinfunction "P$2_M2") (pintype "bidirectional"))
      (node (ref "CN9") (pin "M3") (pinfunction "P$3_M3") (pintype "bidirectional"))
      (node (ref "CN9") (pin "M4") (pinfunction "P$4_M4") (pintype "bidirectional"))
      (node (ref "LED1") (pin "K") (pinfunction "C_K") (pintype "passive"))
      (node (ref "LED2") (pin "K") (pinfunction "C_K") (pintype "passive"))
      (node (ref "LED3") (pin "K") (pinfunction "C_K") (pintype "passive"))
      (node (ref "P1") (pin "P$1") (pinfunction "P_P$1") (pintype "passive"))
      (node (ref "P2") (pin "P$1") (pinfunction "P_P$1") (pintype "passive"))
      (node (ref "P3") (pin "P$1") (pinfunction "P_P$1") (pintype "passive"))
      (node (ref "U1") (pin "15") (pinfunction "VSS_15") (pintype "power_in"))
      (node (ref "U1") (pin "31") (pinfunction "AVSS_31") (pintype "power_in"))
      (node (ref "U1") (pin "36") (pinfunction "VSS_36") (pintype "power_in"))
      (node (ref "U1") (pin "45") (pinfunction "VSS_45") (pintype "power_in"))
      (node (ref "U1") (pin "65") (pinfunction "VSS_65") (pintype "power_in"))
      (node (ref "U1") (pin "75") (pinfunction "VSS_75") (pintype "power_in"))
      (node (ref "U2") (pin "20") (pinfunction "VSS_20") (pintype "power_in"))
      (node (ref "U3") (pin "10") (pinfunction "GND_10") (pintype "power_in"))
    )
    (net (code "95") (name "Net-(LED1-PadA)") (class "Default")
      (node (ref "LED1") (pin "A") (pinfunction "A_A") (pintype "passive"))
      (node (ref "R4") (pin "1") (pinfunction "1_1") (pintype "passive"))
    )
    (net (code "96") (name "Net-(LED2-PadA)") (class "Default")
      (node (ref "LED2") (pin "A") (pinfunction "A_A") (pintype "passive"))
      (node (ref "R5") (pin "1") (pinfunction "1_1") (pintype "passive"))
    )
    (net (code "97") (name "Net-(LED3-PadA)") (class "Default")
      (node (ref "LED3") (pin "A") (pinfunction "A_A") (pintype "passive"))
      (node (ref "R6") (pin "1") (pinfunction "1_1") (pintype "passive"))
    )
    (net (code "98") (name "Net-(LED4-C)") (class "Default")
      (node (ref "LED4") (pin "K") (pinfunction "C_K") (pintype "passive"))
      (node (ref "R2") (pin "2") (pinfunction "2_2") (pintype "passive"))
    )
    (net (code "99") (name "Net-(LED5-C)") (class "Default")
      (node (ref "LED5") (pin "K") (pinfunction "C_K") (pintype "passive"))
      (node (ref "R1") (pin "2") (pinfunction "2_2") (pintype "passive"))
    )
    (net (code "100") (name "Net-(U2-OSCI)") (class "Default")
      (node (ref "C3") (pin "1") (pinfunction "1_1") (pintype "passive"))
      (node (ref "U2") (pin "2") (pinfunction "OSCI_2") (pintype "input"))
      (node (ref "X1") (pin "2") (pinfunction "2_2") (pintype "passive"))
    )
    (net (code "101") (name "Net-(U2-OSCO)") (class "Default")
      (node (ref "C2") (pin "1") (pinfunction "1_1") (pintype "passive"))
      (node (ref "U2") (pin "3") (pinfunction "OSCO_3") (pintype "bidirectional"))
      (node (ref "X1") (pin "1") (pinfunction "1_1") (pintype "passive"))
    )
    (net (code "102") (name "Net-(U2-RXLED{slash}GP6)") (class "Default")
      (node (ref "R1") (pin "1") (pinfunction "1_1") (pintype "passive"))
      (node (ref "U2") (pin "6") (pinfunction "RXLED/GP6_6") (pintype "bidirectional"))
    )
    (net (code "103") (name "Net-(U2-TXLED{slash}GP7)") (class "Default")
      (node (ref "R2") (pin "1") (pinfunction "1_1") (pintype "passive"))
      (node (ref "U2") (pin "5") (pinfunction "TXLED/GP7_5") (pintype "bidirectional"))
    )
    (net (code "104") (name "Net-(U2-VUSB)") (class "Default")
      (node (ref "C4") (pin "1") (pinfunction "1_1") (pintype "passive"))
      (node (ref "U2") (pin "17") (pinfunction "VUSB_17") (pintype "bidirectional"))
    )
    (net (code "105") (name "unconnected-(CN1-Pad26)") (class "Default")
      (node (ref "CN1") (pin "26") (pinfunction "26_26") (pintype "passive"))
    )
    (net (code "106") (name "unconnected-(CN2-Pad26)") (class "Default")
      (node (ref "CN2") (pin "26") (pinfunction "26_26") (pintype "passive"))
    )
    (net (code "107") (name "unconnected-(CN3-Pad26)") (class "Default")
      (node (ref "CN3") (pin "26") (pinfunction "26_26") (pintype "passive"))
    )
    (net (code "108") (name "unconnected-(CN4-Pad26)") (class "Default")
      (node (ref "CN4") (pin "26") (pinfunction "26_26") (pintype "passive"))
    )
    (net (code "109") (name "unconnected-(CN9-Pad1)") (class "Default")
      (node (ref "CN9") (pin "1") (pinfunction "1_1") (pintype "input"))
    )
    (net (code "110") (name "unconnected-(CN9-Pad4)") (class "Default")
      (node (ref "CN9") (pin "4") (pinfunction "4_4") (pintype "input"))
    )
    (net (code "111") (name "unconnected-(U2-GP0-Pad16)") (class "Default")
      (node (ref "U2") (pin "16") (pinfunction "GP0_16") (pintype "bidirectional"))
    )
    (net (code "112") (name "unconnected-(U2-GP1-Pad15)") (class "Default")
      (node (ref "U2") (pin "15") (pinfunction "GP1_15") (pintype "bidirectional"))
    )
    (net (code "113") (name "unconnected-(U2-GP2-Pad14)") (class "Default")
      (node (ref "U2") (pin "14") (pinfunction "GP2_14") (pintype "bidirectional"))
    )
    (net (code "114") (name "unconnected-(U2-GP3-Pad9)") (class "Default")
      (node (ref "U2") (pin "9") (pinfunction "GP3_9") (pintype "bidirectional"))
    )
    (net (code "115") (name "unconnected-(U2-GP4-Pad8)") (class "Default")
      (node (ref "U2") (pin "8") (pinfunction "GP4_8") (pintype "bidirectional"))
    )
    (net (code "116") (name "unconnected-(U2-GP5-Pad7)") (class "Default")
      (node (ref "U2") (pin "7") (pinfunction "GP5_7") (pintype "bidirectional"))
    )
    (net (code "117") (name "unconnected-(U2-~{CTS}-Pad13)") (class "Default")
      (node (ref "U2") (pin "13") (pinfunction "~{CTS}_13") (pintype "input"))
    )
    (net (code "118") (name "unconnected-(U2-~{RTS}-Pad11)") (class "Default")
      (node (ref "U2") (pin "11") (pinfunction "~{RTS}_11") (pintype "bidirectional"))
    )
    (net (code "119") (name "unconnected-(U3-CLKOUT-Pad1)") (class "Default")
      (node (ref "U3") (pin "1") (pinfunction "CLKOUT_1") (pintype "output"))
    )
    (net (code "120") (name "unconnected-(U3-WOL-Pad3)") (class "Default")
      (node (ref "U3") (pin "3") (pinfunction "WOL_3") (pintype "output"))
    )
  )
)
